# Debugger.net
KiCad netlist of a schematic drawn in Altium Designer
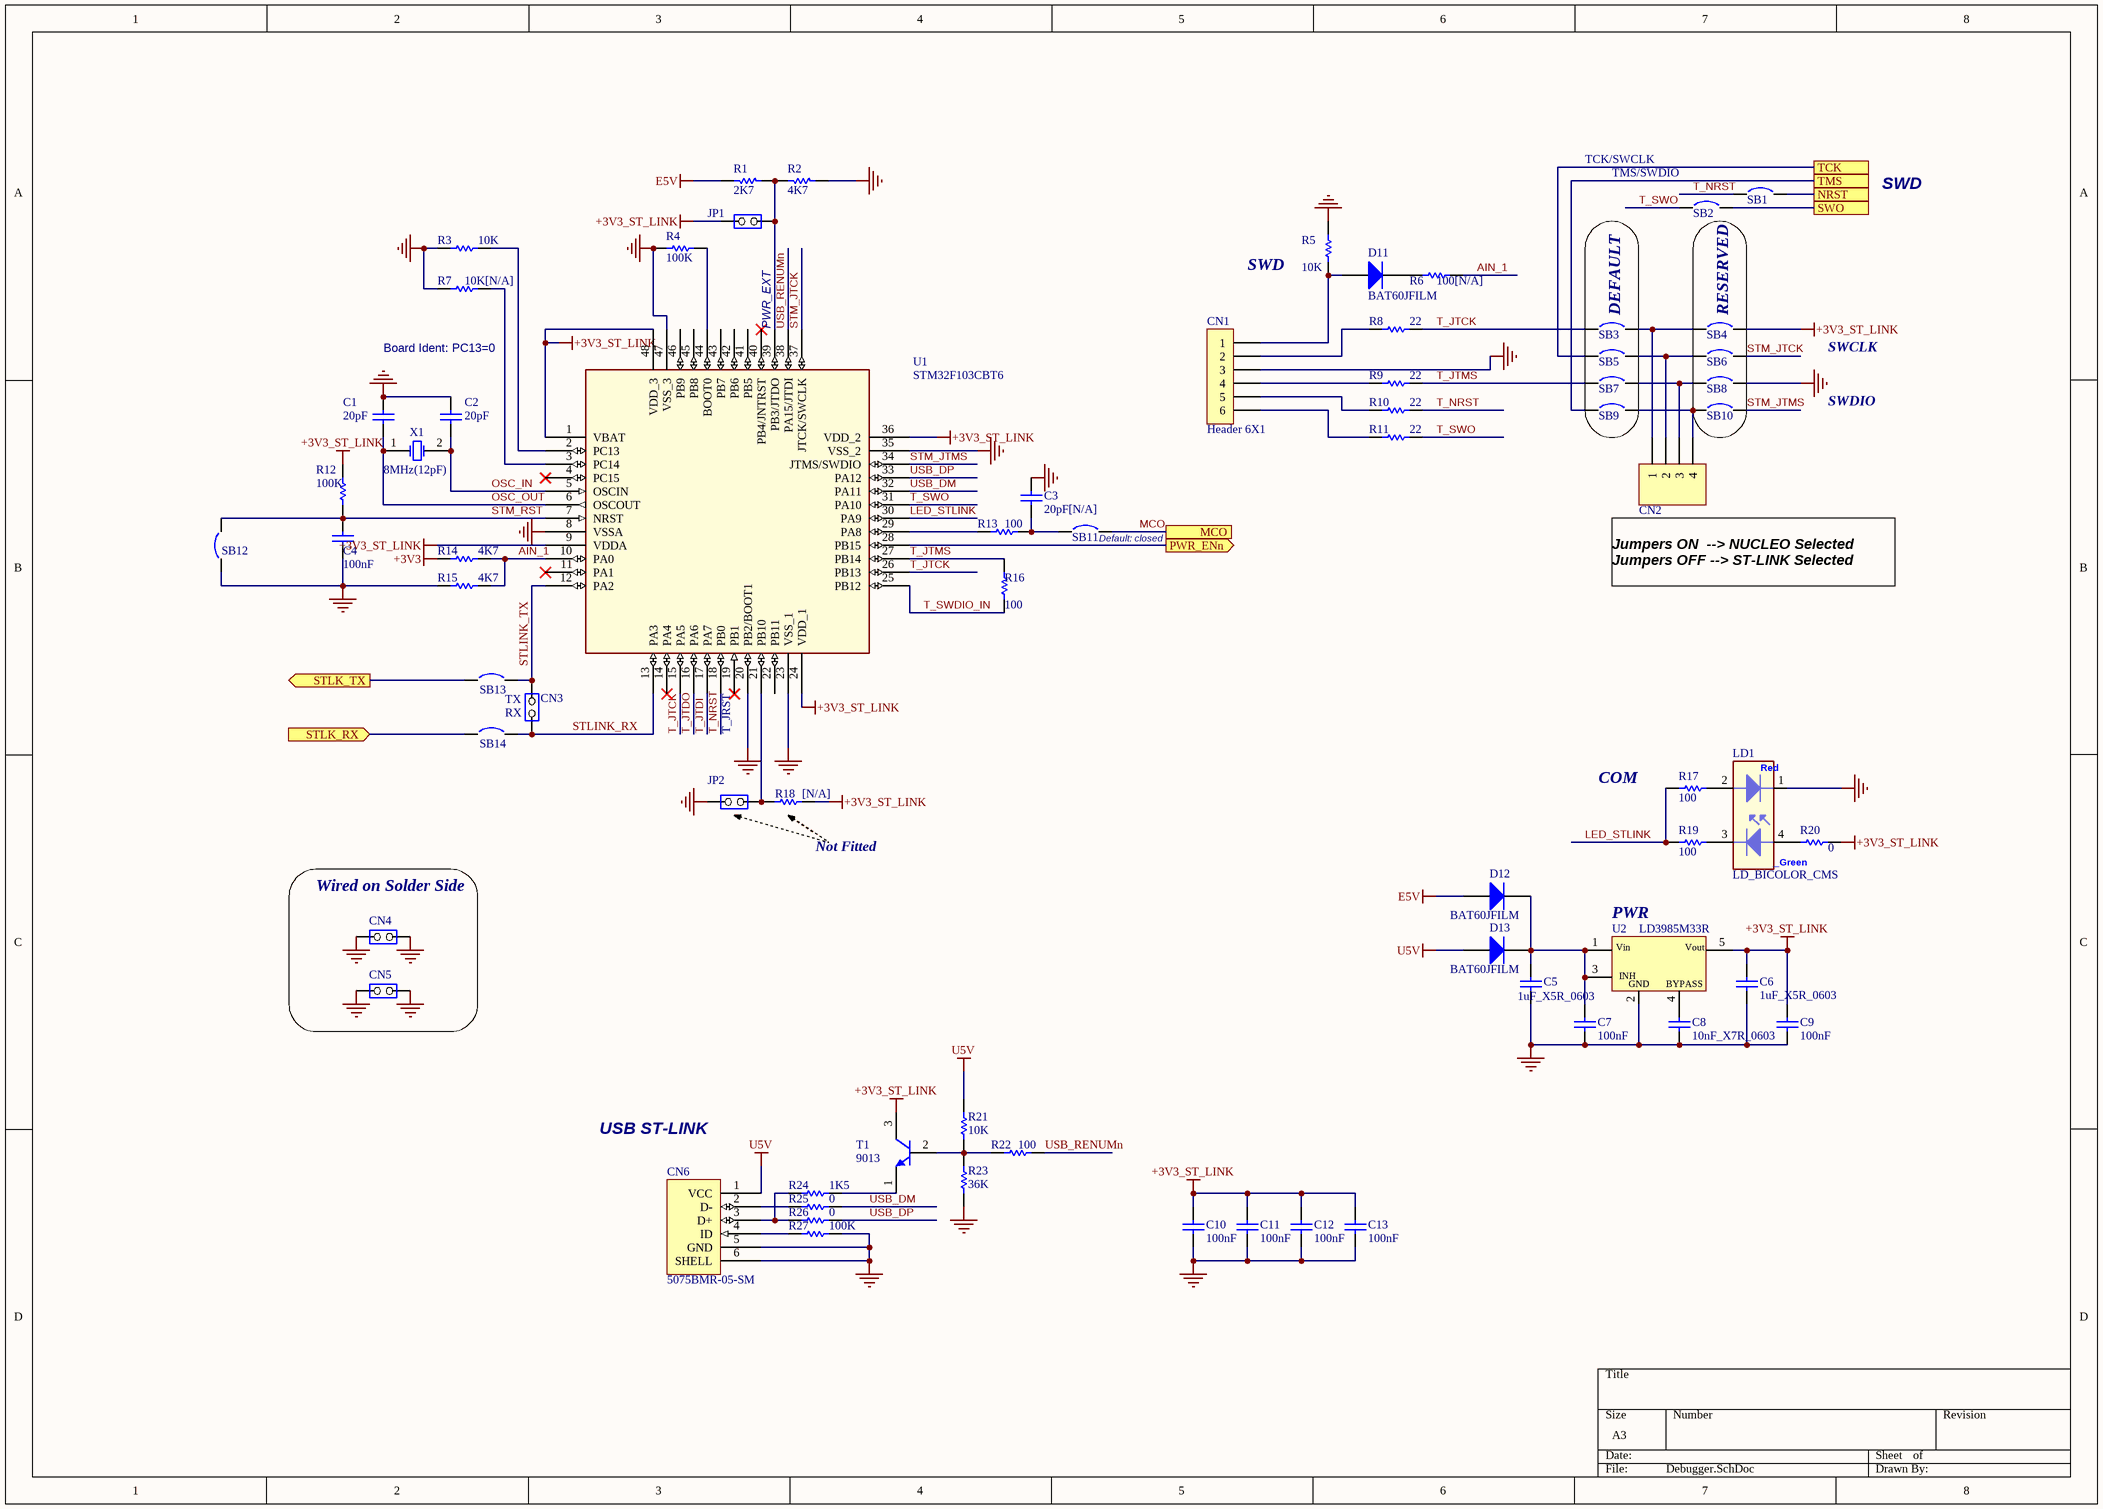
[diagram p0: Debugger.SchDoc]

(export (version "E")
  (design (tool "Eeschema 10.0.6"))
  (components
    (comp (ref "C1")
      (value "20pF")
      (footprint "0603C")
      (description "Capacitor 0402 / 0603 / 0805")
      (libsource (lib "MCD_TOOLS") (part "Capacitor_ST"))
    )
    (comp (ref "C2")
      (value "20pF")
      (footprint "0603C")
      (description "Capacitor 0402 / 0603 / 0805")
      (libsource (lib "MCD_TOOLS") (part "Capacitor_ST"))
    )
    (comp (ref "C3")
      (value "20pF[N/A]")
      (footprint "0603C")
      (description "Capacitor 0402 / 0603 / 0805")
      (libsource (lib "MCD_TOOLS") (part "Capacitor_ST"))
    )
    (comp (ref "C4")
      (value "100nF")
      (footprint "0603C")
      (description "Capacitor 0402 / 0603 / 0805")
      (libsource (lib "MCD_TOOLS") (part "Capacitor_ST"))
    )
    (comp (ref "C5")
      (value "1uF_X5R_0603")
      (footprint "0603C")
      (description "0603  X5R 1µF")
      (fields (field (name "TOLERANCE") "10%"))
      (libsource (lib "MB963_1") (part "CAP SMD 0603  X5R 1µF 25V 10%"))
    )
    (comp (ref "C6")
      (value "1uF_X5R_0603")
      (footprint "0603C")
      (description "0603  X5R 1µF")
      (fields (field (name "TOLERANCE") "10%"))
      (libsource (lib "MB963_1") (part "CAP SMD 0603  X5R 1µF 25V 10%"))
    )
    (comp (ref "C7")
      (value "100nF")
      (footprint "0603C")
      (description "Capacitor 0402 / 0603 / 0805")
      (libsource (lib "MCD_TOOLS") (part "Capacitor_ST"))
    )
    (comp (ref "C8")
      (value "10nF_X7R_0603")
      (footprint "0603C")
      (description "0603  X7R 10NF")
      (fields (field (name "TOLERANCE") "10%"))
      (libsource (lib "MB963_1") (part "CAP SMD 0603  X7R 10000PF 50V 10%"))
    )
    (comp (ref "C9")
      (value "100nF")
      (footprint "0603C")
      (description "Capacitor 0402 / 0603 / 0805")
      (libsource (lib "MCD_TOOLS") (part "Capacitor_ST"))
    )
    (comp (ref "C10")
      (value "100nF")
      (footprint "0603C")
      (description "Capacitor 0402 / 0603 / 0805")
      (libsource (lib "MCD_TOOLS") (part "Capacitor_ST"))
    )
    (comp (ref "C11")
      (value "100nF")
      (footprint "0603C")
      (description "Capacitor 0402 / 0603 / 0805")
      (libsource (lib "MCD_TOOLS") (part "Capacitor_ST"))
    )
    (comp (ref "C12")
      (value "100nF")
      (footprint "0603C")
      (description "Capacitor 0402 / 0603 / 0805")
      (libsource (lib "MCD_TOOLS") (part "Capacitor_ST"))
    )
    (comp (ref "C13")
      (value "100nF")
      (footprint "0603C")
      (description "Capacitor 0402 / 0603 / 0805")
      (libsource (lib "MCD_TOOLS") (part "Capacitor_ST"))
    )
    (comp (ref "CN1")
      (value "Header 6X1")
      (footprint "1*6P")
      (description "Header, 6-Pin, Single row")
      (fields (field (name "PUBLISHER") "Altium Limited"))
      (libsource (lib "Nucleo_64") (part "Header 6X1"))
    )
    (comp (ref "CN2")
      (value "Header 4")
      (footprint "1*4")
      (description "Header, 4-Pin, Single row")
      (fields (field (name "PUBLISHER") "Altium Limited"))
      (libsource (lib "Nucleo_64") (part "Header 4"))
    )
    (comp (ref "CN3") (value "~") (footprint "SIP2/2.54") (libsource (lib "MCD_TOOLS") (part "JP2")))
    (comp (ref "CN4") (value "~") (footprint "SIP2/2.54") (libsource (lib "*") (part "JP2")))
    (comp (ref "CN5") (value "~") (footprint "SIP2/2.54") (libsource (lib "*") (part "JP2")))
    (comp (ref "CN6")
      (value "5075BMR-05-SM")
      (footprint "USB-MINI-B-SMD")
      (description "USB-MINI-typeB connector")
      (libsource (lib "MCD_TOOLS") (part "USB-MINI-typeB connector"))
    )
    (comp (ref "D11")
      (value "BAT60JFILM")
      (footprint "SOD323/A")
      (libsource (lib "MCD_TOOLS") (part "BAT60JFILM"))
    )
    (comp (ref "D12")
      (value "BAT60JFILM")
      (footprint "SOD323/A")
      (libsource (lib "MCD_TOOLS") (part "BAT60JFILM"))
    )
    (comp (ref "D13")
      (value "BAT60JFILM")
      (footprint "SOD323/A")
      (libsource (lib "MCD_TOOLS") (part "BAT60JFILM"))
    )
    (comp (ref "JP1") (value "~") (footprint "SIP2/2.54") (libsource (lib "*") (part "JP2")))
    (comp (ref "JP2") (value "~") (footprint "SIP2/2.54") (libsource (lib "*") (part "JP2")))
    (comp (ref "LD1")
      (value "LD_BICOLOR_CMS")
      (footprint "HSMF-A201")
      (description "Bicolor Led")
      (libsource (lib "MCD_TOOLS") (part "LD_BICOLOR_CMS"))
    )
    (comp (ref "R1")
      (value "2K7")
      (footprint "0603R")
      (description "Resistor")
      (fields (field (name "PUBLISHER") "Altium Limited"))
      (libsource (lib "Miscellaneous Devices") (part "Res1"))
    )
    (comp (ref "R2")
      (value "4K7")
      (footprint "0603R")
      (description "Resistor")
      (fields (field (name "PUBLISHER") "Altium Limited"))
      (libsource (lib "Miscellaneous Devices") (part "Res1"))
    )
    (comp (ref "R3")
      (value "10K")
      (footprint "0603R")
      (description "Resistor 0402 / 0603 / 0805")
      (libsource (lib "") (part "Res1_2"))
    )
    (comp (ref "R4")
      (value "100K")
      (footprint "0603R")
      (description "Resistor 0402 / 0603 / 0805")
      (libsource (lib "") (part "Res1_2"))
    )
    (comp (ref "R5")
      (value "10K")
      (footprint "0603R")
      (description "Resistor 0402 / 0603 / 0805")
      (libsource (lib "") (part "Res1_2"))
    )
    (comp (ref "R6")
      (value "100[N/A]")
      (footprint "0603R")
      (description "Resistor 0402 / 0603 / 0805")
      (libsource (lib "") (part "Res1_2"))
    )
    (comp (ref "R7")
      (value "10K[N/A]")
      (footprint "0603R")
      (description "Resistor 0402 / 0603 / 0805")
      (libsource (lib "") (part "Res1_2"))
    )
    (comp (ref "R8")
      (value "22")
      (footprint "0603R")
      (description "Resistor 0402 / 0603 / 0805")
      (libsource (lib "") (part "Res1_2"))
    )
    (comp (ref "R9")
      (value "22")
      (footprint "0603R")
      (description "Resistor 0402 / 0603 / 0805")
      (libsource (lib "") (part "Res1_2"))
    )
    (comp (ref "R10")
      (value "22")
      (footprint "0603R")
      (description "Resistor 0402 / 0603 / 0805")
      (libsource (lib "") (part "Res1_2"))
    )
    (comp (ref "R11")
      (value "22")
      (footprint "0603R")
      (description "Resistor 0402 / 0603 / 0805")
      (libsource (lib "") (part "Res1_2"))
    )
    (comp (ref "R12")
      (value "100K")
      (footprint "0603R")
      (description "Resistor 0402 / 0603 / 0805")
      (libsource (lib "") (part "Res1_2"))
    )
    (comp (ref "R13")
      (value "100")
      (footprint "0603R")
      (description "Resistor 0402 / 0603 / 0805")
      (libsource (lib "") (part "Res1_2"))
    )
    (comp (ref "R14")
      (value "4K7")
      (footprint "0603R")
      (description "Resistor 0402 / 0603 / 0805")
      (libsource (lib "") (part "Res1_2"))
    )
    (comp (ref "R15")
      (value "4K7")
      (footprint "0603R")
      (description "Resistor 0402 / 0603 / 0805")
      (libsource (lib "") (part "Res1_2"))
    )
    (comp (ref "R16")
      (value "100")
      (footprint "0603R")
      (description "Resistor 0402 / 0603 / 0805")
      (libsource (lib "") (part "Res1_2"))
    )
    (comp (ref "R17")
      (value "100")
      (footprint "0603R")
      (description "Resistor 0402 / 0603 / 0805")
      (libsource (lib "") (part "Res1_2"))
    )
    (comp (ref "R18")
      (value "[N/A]")
      (footprint "0603R")
      (description "Resistor")
      (fields (field (name "PUBLISHER") "Altium Limited"))
      (libsource (lib "") (part "Res1_1"))
    )
    (comp (ref "R19")
      (value "100")
      (footprint "0603R")
      (description "Resistor 0402 / 0603 / 0805")
      (libsource (lib "") (part "Res1_2"))
    )
    (comp (ref "R20")
      (value "0")
      (footprint "0603R")
      (description "Resistor 0402 / 0603 / 0805")
      (libsource (lib "") (part "Res1_2"))
    )
    (comp (ref "R21")
      (value "10K")
      (footprint "0603R")
      (description "Resistor")
      (fields (field (name "PUBLISHER") "Altium Limited"))
      (libsource (lib "") (part "Res1_1"))
    )
    (comp (ref "R22")
      (value "100")
      (footprint "0603R")
      (description "Resistor 0402 / 0603 / 0805")
      (libsource (lib "") (part "Res1_2"))
    )
    (comp (ref "R23")
      (value "36K")
      (footprint "0603R")
      (description "Resistor")
      (fields (field (name "PUBLISHER") "Altium Limited"))
      (libsource (lib "") (part "Res1_1"))
    )
    (comp (ref "R24")
      (value "1K5")
      (footprint "0603R")
      (description "Resistor 0402 / 0603 / 0805")
      (libsource (lib "") (part "Res1_2"))
    )
    (comp (ref "R25")
      (value "0")
      (footprint "0603R")
      (description "Resistor 0402 / 0603 / 0805")
      (libsource (lib "") (part "Res1_2"))
    )
    (comp (ref "R26")
      (value "0")
      (footprint "0603R")
      (description "Resistor 0402 / 0603 / 0805")
      (libsource (lib "") (part "Res1_2"))
    )
    (comp (ref "R27")
      (value "100K")
      (footprint "0603R")
      (description "Resistor 0402 / 0603 / 0805")
      (libsource (lib "") (part "Res1_2"))
    )
    (comp (ref "SB1")
      (value "Circuit Breaker")
      (footprint "JP2_SMD")
      (fields (field (name "PUBLISHER") "Altium Limited"))
      (libsource (lib "MB915") (part "Circuit Breaker"))
    )
    (comp (ref "SB2")
      (value "Circuit Breaker")
      (footprint "JP2_SMD")
      (fields (field (name "PUBLISHER") "Altium Limited"))
      (libsource (lib "MCD_TOOLS") (part "Circuit Breaker"))
    )
    (comp (ref "SB3")
      (value "Circuit Breaker")
      (footprint "JP2_SMD")
      (fields (field (name "PUBLISHER") "Altium Limited"))
      (libsource (lib "MB915") (part "Circuit Breaker"))
    )
    (comp (ref "SB4")
      (value "Circuit Breaker")
      (footprint "JP2_SMD")
      (fields (field (name "PUBLISHER") "Altium Limited"))
      (libsource (lib "MB915") (part "Circuit Breaker"))
    )
    (comp (ref "SB5")
      (value "Circuit Breaker")
      (footprint "JP2_SMD")
      (fields (field (name "PUBLISHER") "Altium Limited"))
      (libsource (lib "MB915") (part "Circuit Breaker"))
    )
    (comp (ref "SB6")
      (value "Circuit Breaker")
      (footprint "JP2_SMD")
      (fields (field (name "PUBLISHER") "Altium Limited"))
      (libsource (lib "MB915") (part "Circuit Breaker"))
    )
    (comp (ref "SB7")
      (value "Circuit Breaker")
      (footprint "JP2_SMD")
      (fields (field (name "PUBLISHER") "Altium Limited"))
      (libsource (lib "MB915") (part "Circuit Breaker"))
    )
    (comp (ref "SB8")
      (value "Circuit Breaker")
      (footprint "JP2_SMD")
      (fields (field (name "PUBLISHER") "Altium Limited"))
      (libsource (lib "MB915") (part "Circuit Breaker"))
    )
    (comp (ref "SB9")
      (value "Circuit Breaker")
      (footprint "JP2_SMD")
      (fields (field (name "PUBLISHER") "Altium Limited"))
      (libsource (lib "MB915") (part "Circuit Breaker"))
    )
    (comp (ref "SB10")
      (value "Circuit Breaker")
      (footprint "JP2_SMD")
      (fields (field (name "PUBLISHER") "Altium Limited"))
      (libsource (lib "MB915") (part "Circuit Breaker"))
    )
    (comp (ref "SB11")
      (value "Circuit Breaker")
      (footprint "JP2_SMD")
      (fields (field (name "PUBLISHER") "Altium Limited"))
      (libsource (lib "MCD_TOOLS") (part "Circuit Breaker"))
    )
    (comp (ref "SB12")
      (value "Circuit Breaker")
      (footprint "JP2_SMD")
      (fields (field (name "PUBLISHER") "Altium Limited"))
      (libsource (lib "MB915") (part "Circuit Breaker"))
    )
    (comp (ref "SB13")
      (value "Circuit Breaker")
      (footprint "JP2_SMD")
      (fields (field (name "PUBLISHER") "Altium Limited"))
      (libsource (lib "MCD_TOOLS") (part "Circuit Breaker"))
    )
    (comp (ref "SB14")
      (value "Circuit Breaker")
      (footprint "JP2_SMD")
      (fields (field (name "PUBLISHER") "Altium Limited"))
      (libsource (lib "MCD_TOOLS") (part "Circuit Breaker"))
    )
    (comp (ref "T1")
      (value "9013")
      (footprint "SOT-23")
      (description "NPN Bipolar Transistor")
      (fields (field (name "PUBLISHER") "Altium Limited"))
      (libsource (lib "Miscellaneous Devices") (part "NPN"))
    )
    (comp (ref "U1")
      (value "STM32F103CBT6")
      (footprint "QFP48 7X7")
      (description "Medium-density performance line ARM-based 32-bit MCU with 64KB Flash")
      (libsource (lib "Nucleo_64") (part "STM32F103CBT6"))
    )
    (comp (ref "U2")
      (value "LD3985M33R")
      (footprint "SOT-23-5L")
      (description "Ultra low drop-low noise BiCMOS voltage, regulators low ESR capacitors compatible")
      (libsource (lib "MCD_TOOLS") (part "LD3985M33R"))
    )
    (comp (ref "X1")
      (value "8MHz(12pF)")
      (footprint "XTAL1")
      (description "Crystal Oscillator")
      (fields (field (name "PUBLISHER") "Altium Limited"))
      (libsource (lib "MB963_1") (part "XTAL"))
    )
  )
  (nets
    (net (code "1") (name "+3V3") (class "Default")
      (node (ref "R14") (pin "1") (pinfunction "1_1") (pintype "passive"))
    )
    (net (code "2") (name "+3V3_ST_LINK") (class "Default")
      (node (ref "C10") (pin "2") (pinfunction "2_2") (pintype "passive"))
      (node (ref "C11") (pin "2") (pinfunction "2_2") (pintype "passive"))
      (node (ref "C12") (pin "2") (pinfunction "2_2") (pintype "passive"))
      (node (ref "C13") (pin "2") (pinfunction "2_2") (pintype "passive"))
      (node (ref "C6") (pin "1") (pinfunction "1_1") (pintype "passive"))
      (node (ref "C9") (pin "2") (pinfunction "2_2") (pintype "passive"))
      (node (ref "JP1") (pin "1") (pinfunction "COMMON_1") (pintype "passive"))
      (node (ref "R12") (pin "2") (pinfunction "2_2") (pintype "passive"))
      (node (ref "R18") (pin "1") (pinfunction "1_1") (pintype "passive"))
      (node (ref "R20") (pin "2") (pinfunction "2_2") (pintype "passive"))
      (node (ref "SB4") (pin "2") (pinfunction "2_2") (pintype "passive"))
      (node (ref "T1") (pin "3") (pinfunction "C_3") (pintype "passive"))
      (node (ref "U1") (pin "1") (pinfunction "VBAT_1") (pintype "power_in"))
      (node (ref "U1") (pin "24") (pinfunction "VDD_1_24") (pintype "power_in"))
      (node (ref "U1") (pin "36") (pinfunction "VDD_2_36") (pintype "power_in"))
      (node (ref "U1") (pin "48") (pinfunction "VDD_3_48") (pintype "power_in"))
      (node (ref "U1") (pin "9") (pinfunction "VDDA_9") (pintype "power_in"))
      (node (ref "U2") (pin "5") (pinfunction "Vout_5") (pintype "passive"))
    )
    (net (code "3") (name "/AIN_1") (class "Default")
      (node (ref "R14") (pin "2") (pinfunction "2_2") (pintype "passive"))
      (node (ref "R15") (pin "2") (pinfunction "2_2") (pintype "passive"))
      (node (ref "R6") (pin "2") (pinfunction "2_2") (pintype "passive"))
      (node (ref "U1") (pin "10") (pinfunction "PA0_10") (pintype "bidirectional"))
    )
    (net (code "4") (name "/LED_STLINK") (class "Default")
      (node (ref "R17") (pin "1") (pinfunction "1_1") (pintype "passive"))
      (node (ref "R19") (pin "1") (pinfunction "1_1") (pintype "passive"))
      (node (ref "U1") (pin "30") (pinfunction "PA9_30") (pintype "bidirectional"))
    )
    (net (code "5") (name "/MCO") (class "Default")
      (node (ref "SB11") (pin "2") (pinfunction "2_2") (pintype "passive"))
    )
    (net (code "6") (name "/NRST") (class "Default")
      (node (ref "SB1") (pin "2") (pinfunction "2_2") (pintype "passive"))
    )
    (net (code "7") (name "/OSC_IN") (class "Default")
      (node (ref "C2") (pin "1") (pinfunction "1_1") (pintype "passive"))
      (node (ref "U1") (pin "5") (pinfunction "OSCIN_5") (pintype "input"))
      (node (ref "X1") (pin "2") (pinfunction "OSC2_2") (pintype "passive"))
    )
    (net (code "8") (name "/OSC_OUT") (class "Default")
      (node (ref "C1") (pin "1") (pinfunction "1_1") (pintype "passive"))
      (node (ref "U1") (pin "6") (pinfunction "OSCOUT_6") (pintype "output"))
      (node (ref "X1") (pin "1") (pinfunction "OSC1_1") (pintype "passive"))
    )
    (net (code "9") (name "/PWR_ENn") (class "Default")
      (node (ref "U1") (pin "28") (pinfunction "PB15_28") (pintype "bidirectional"))
    )
    (net (code "10") (name "/STLINK_RX") (class "Default")
      (node (ref "CN3") (pin "1") (pinfunction "COMMON_1") (pintype "passive"))
      (node (ref "SB14") (pin "2") (pinfunction "2_2") (pintype "passive"))
      (node (ref "U1") (pin "13") (pinfunction "PA3_13") (pintype "bidirectional"))
    )
    (net (code "11") (name "/STLINK_TX") (class "Default")
      (node (ref "CN3") (pin "2") (pinfunction "NO_2") (pintype "passive"))
      (node (ref "SB13") (pin "2") (pinfunction "2_2") (pintype "passive"))
      (node (ref "U1") (pin "12") (pinfunction "PA2_12") (pintype "bidirectional"))
    )
    (net (code "12") (name "/STLK_RX") (class "Default")
      (node (ref "SB14") (pin "1") (pinfunction "1_1") (pintype "passive"))
    )
    (net (code "13") (name "/STLK_TX") (class "Default")
      (node (ref "SB13") (pin "1") (pinfunction "1_1") (pintype "passive"))
    )
    (net (code "14") (name "/STM_JTCK") (class "Default")
      (node (ref "SB6") (pin "2") (pinfunction "2_2") (pintype "passive"))
      (node (ref "U1") (pin "37") (pinfunction "JTCK/SWCLK_37") (pintype "bidirectional"))
    )
    (net (code "15") (name "/STM_JTMS") (class "Default")
      (node (ref "SB10") (pin "2") (pinfunction "2_2") (pintype "passive"))
      (node (ref "U1") (pin "34") (pinfunction "JTMS/SWDIO_34") (pintype "bidirectional"))
    )
    (net (code "16") (name "/STM_RST") (class "Default")
      (node (ref "C4") (pin "2") (pinfunction "2_2") (pintype "passive"))
      (node (ref "R12") (pin "1") (pinfunction "1_1") (pintype "passive"))
      (node (ref "SB12") (pin "2") (pinfunction "2_2") (pintype "passive"))
      (node (ref "U1") (pin "7") (pinfunction "NRST_7") (pintype "input"))
    )
    (net (code "17") (name "/SWO") (class "Default")
      (node (ref "SB2") (pin "2") (pinfunction "2_2") (pintype "passive"))
    )
    (net (code "18") (name "/TCK") (class "Default")
      (node (ref "SB5") (pin "1") (pinfunction "1_1") (pintype "passive"))
    )
    (net (code "19") (name "/TMS") (class "Default")
      (node (ref "SB9") (pin "1") (pinfunction "1_1") (pintype "passive"))
    )
    (net (code "20") (name "/T_JTCK") (class "Default")
      (node (ref "R8") (pin "2") (pinfunction "2_2") (pintype "passive"))
      (node (ref "SB3") (pin "1") (pinfunction "1_1") (pintype "passive"))
      (node (ref "U1") (pin "15") (pinfunction "PA5_15") (pintype "bidirectional"))
      (node (ref "U1") (pin "26") (pinfunction "PB13_26") (pintype "bidirectional"))
    )
    (net (code "21") (name "/T_JTDI") (class "Default")
      (node (ref "U1") (pin "17") (pinfunction "PA7_17") (pintype "bidirectional"))
    )
    (net (code "22") (name "/T_JTDO") (class "Default")
      (node (ref "U1") (pin "16") (pinfunction "PA6_16") (pintype "bidirectional"))
    )
    (net (code "23") (name "/T_JTMS") (class "Default")
      (node (ref "R16") (pin "2") (pinfunction "2_2") (pintype "passive"))
      (node (ref "R9") (pin "2") (pinfunction "2_2") (pintype "passive"))
      (node (ref "SB7") (pin "1") (pinfunction "1_1") (pintype "passive"))
      (node (ref "U1") (pin "27") (pinfunction "PB14_27") (pintype "bidirectional"))
    )
    (net (code "24") (name "/T_NRST") (class "Default")
      (node (ref "R10") (pin "2") (pinfunction "2_2") (pintype "passive"))
      (node (ref "SB1") (pin "1") (pinfunction "1_1") (pintype "passive"))
      (node (ref "U1") (pin "18") (pinfunction "PB0_18") (pintype "bidirectional"))
    )
    (net (code "25") (name "/T_SWDIO_IN") (class "Default")
      (node (ref "R16") (pin "1") (pinfunction "1_1") (pintype "passive"))
      (node (ref "U1") (pin "25") (pinfunction "PB12_25") (pintype "bidirectional"))
    )
    (net (code "26") (name "/T_SWO") (class "Default")
      (node (ref "R11") (pin "2") (pinfunction "2_2") (pintype "passive"))
      (node (ref "SB2") (pin "1") (pinfunction "1_1") (pintype "passive"))
      (node (ref "U1") (pin "31") (pinfunction "PA10_31") (pintype "bidirectional"))
    )
    (net (code "27") (name "/USB_DM") (class "Default")
      (node (ref "R25") (pin "2") (pinfunction "2_2") (pintype "passive"))
      (node (ref "U1") (pin "32") (pinfunction "PA11_32") (pintype "bidirectional"))
    )
    (net (code "28") (name "/USB_DP") (class "Default")
      (node (ref "R26") (pin "2") (pinfunction "2_2") (pintype "passive"))
      (node (ref "U1") (pin "33") (pinfunction "PA12_33") (pintype "bidirectional"))
    )
    (net (code "29") (name "/USB_RENUMn") (class "Default")
      (node (ref "R22") (pin "2") (pinfunction "2_2") (pintype "passive"))
      (node (ref "U1") (pin "38") (pinfunction "PA15/JTDI_38") (pintype "bidirectional"))
    )
    (net (code "30") (name "E5V") (class "Default")
      (node (ref "D12") (pin "1") (pinfunction "A_1") (pintype "passive"))
      (node (ref "R1") (pin "1") (pinfunction "1_1") (pintype "passive"))
    )
    (net (code "31") (name "GND") (class "Default")
      (node (ref "C1") (pin "2") (pinfunction "2_2") (pintype "passive"))
      (node (ref "C10") (pin "1") (pinfunction "1_1") (pintype "passive"))
      (node (ref "C11") (pin "1") (pinfunction "1_1") (pintype "passive"))
      (node (ref "C12") (pin "1") (pinfunction "1_1") (pintype "passive"))
      (node (ref "C13") (pin "1") (pinfunction "1_1") (pintype "passive"))
      (node (ref "C2") (pin "2") (pinfunction "2_2") (pintype "passive"))
      (node (ref "C3") (pin "2") (pinfunction "2_2") (pintype "passive"))
      (node (ref "C4") (pin "1") (pinfunction "1_1") (pintype "passive"))
      (node (ref "C5") (pin "1") (pinfunction "1_1") (pintype "passive"))
      (node (ref "C6") (pin "2") (pinfunction "2_2") (pintype "passive"))
      (node (ref "C7") (pin "1") (pinfunction "1_1") (pintype "passive"))
      (node (ref "C8") (pin "1") (pinfunction "1_1") (pintype "passive"))
      (node (ref "C9") (pin "1") (pinfunction "1_1") (pintype "passive"))
      (node (ref "CN1") (pin "3") (pinfunction "3_3") (pintype "passive"))
      (node (ref "CN4") (pin "1") (pinfunction "COMMON_1") (pintype "passive"))
      (node (ref "CN4") (pin "2") (pinfunction "NO_2") (pintype "passive"))
      (node (ref "CN5") (pin "1") (pinfunction "COMMON_1") (pintype "passive"))
      (node (ref "CN5") (pin "2") (pinfunction "NO_2") (pintype "passive"))
      (node (ref "CN6") (pin "5") (pinfunction "GND_5") (pintype "power_in"))
      (node (ref "CN6") (pin "6") (pinfunction "SHELL_6") (pintype "power_in"))
      (node (ref "JP2") (pin "1") (pinfunction "COMMON_1") (pintype "passive"))
      (node (ref "LD1") (pin "1") (pinfunction "1_1") (pintype "passive"))
      (node (ref "R15") (pin "1") (pinfunction "1_1") (pintype "passive"))
      (node (ref "R2") (pin "2") (pinfunction "2_2") (pintype "passive"))
      (node (ref "R23") (pin "1") (pinfunction "1_1") (pintype "passive"))
      (node (ref "R27") (pin "2") (pinfunction "2_2") (pintype "passive"))
      (node (ref "R3") (pin "1") (pinfunction "1_1") (pintype "passive"))
      (node (ref "R4") (pin "1") (pinfunction "1_1") (pintype "passive"))
      (node (ref "R5") (pin "2") (pinfunction "2_2") (pintype "passive"))
      (node (ref "R7") (pin "1") (pinfunction "1_1") (pintype "passive"))
      (node (ref "SB12") (pin "1") (pinfunction "1_1") (pintype "passive"))
      (node (ref "SB8") (pin "2") (pinfunction "2_2") (pintype "passive"))
      (node (ref "U1") (pin "20") (pinfunction "PB2/BOOT1_20") (pintype "bidirectional"))
      (node (ref "U1") (pin "23") (pinfunction "VSS_1_23") (pintype "power_in"))
      (node (ref "U1") (pin "35") (pinfunction "VSS_2_35") (pintype "power_in"))
      (node (ref "U1") (pin "47") (pinfunction "VSS_3_47") (pintype "power_in"))
      (node (ref "U1") (pin "8") (pinfunction "VSSA_8") (pintype "power_in"))
      (node (ref "U2") (pin "2") (pinfunction "GND_2") (pintype "passive"))
    )
    (net (code "32") (name "Net-(C3-Pad1)") (class "Default")
      (node (ref "C3") (pin "1") (pinfunction "1_1") (pintype "passive"))
      (node (ref "R13") (pin "2") (pinfunction "2_2") (pintype "passive"))
      (node (ref "SB11") (pin "1") (pinfunction "1_1") (pintype "passive"))
    )
    (net (code "33") (name "Net-(CN1-Pad2)") (class "Default")
      (node (ref "CN1") (pin "2") (pinfunction "2_2") (pintype "passive"))
      (node (ref "R8") (pin "1") (pinfunction "1_1") (pintype "passive"))
    )
    (net (code "34") (name "Net-(CN1-Pad4)") (class "Default")
      (node (ref "CN1") (pin "4") (pinfunction "4_4") (pintype "passive"))
      (node (ref "R9") (pin "1") (pinfunction "1_1") (pintype "passive"))
    )
    (net (code "35") (name "Net-(CN1-Pad5)") (class "Default")
      (node (ref "CN1") (pin "5") (pinfunction "5_5") (pintype "passive"))
      (node (ref "R10") (pin "1") (pinfunction "1_1") (pintype "passive"))
    )
    (net (code "36") (name "Net-(CN1-Pad6)") (class "Default")
      (node (ref "CN1") (pin "6") (pinfunction "6_6") (pintype "passive"))
      (node (ref "R11") (pin "1") (pinfunction "1_1") (pintype "passive"))
    )
    (net (code "37") (name "Net-(CN2-Pad1)") (class "Default")
      (node (ref "CN2") (pin "1") (pinfunction "1_1") (pintype "passive"))
      (node (ref "SB3") (pin "2") (pinfunction "2_2") (pintype "passive"))
      (node (ref "SB4") (pin "1") (pinfunction "1_1") (pintype "passive"))
    )
    (net (code "38") (name "Net-(CN2-Pad2)") (class "Default")
      (node (ref "CN2") (pin "2") (pinfunction "2_2") (pintype "passive"))
      (node (ref "SB5") (pin "2") (pinfunction "2_2") (pintype "passive"))
      (node (ref "SB6") (pin "1") (pinfunction "1_1") (pintype "passive"))
    )
    (net (code "39") (name "Net-(CN2-Pad3)") (class "Default")
      (node (ref "CN2") (pin "3") (pinfunction "3_3") (pintype "passive"))
      (node (ref "SB7") (pin "2") (pinfunction "2_2") (pintype "passive"))
      (node (ref "SB8") (pin "1") (pinfunction "1_1") (pintype "passive"))
    )
    (net (code "40") (name "Net-(CN2-Pad4)") (class "Default")
      (node (ref "CN2") (pin "4") (pinfunction "4_4") (pintype "passive"))
      (node (ref "SB10") (pin "1") (pinfunction "1_1") (pintype "passive"))
      (node (ref "SB9") (pin "2") (pinfunction "2_2") (pintype "passive"))
    )
    (net (code "41") (name "Net-(CN6-D+)") (class "Default")
      (node (ref "CN6") (pin "3") (pinfunction "D+_3") (pintype "bidirectional"))
      (node (ref "R24") (pin "1") (pinfunction "1_1") (pintype "passive"))
      (node (ref "R26") (pin "1") (pinfunction "1_1") (pintype "passive"))
    )
    (net (code "42") (name "Net-(CN6-D-)") (class "Default")
      (node (ref "CN6") (pin "2") (pinfunction "D-_2") (pintype "bidirectional"))
      (node (ref "R25") (pin "1") (pinfunction "1_1") (pintype "passive"))
    )
    (net (code "43") (name "Net-(CN6-ID)") (class "Default")
      (node (ref "CN6") (pin "4") (pinfunction "ID_4") (pintype "input"))
      (node (ref "R27") (pin "1") (pinfunction "1_1") (pintype "passive"))
    )
    (net (code "44") (name "Net-(D11-A)") (class "Default")
      (node (ref "CN1") (pin "1") (pinfunction "1_1") (pintype "passive"))
      (node (ref "D11") (pin "1") (pinfunction "A_1") (pintype "passive"))
      (node (ref "R5") (pin "1") (pinfunction "1_1") (pintype "passive"))
    )
    (net (code "45") (name "Net-(D11-K)") (class "Default")
      (node (ref "D11") (pin "2") (pinfunction "K_2") (pintype "passive"))
      (node (ref "R6") (pin "1") (pinfunction "1_1") (pintype "passive"))
    )
    (net (code "46") (name "Net-(D12-K)") (class "Default")
      (node (ref "C5") (pin "2") (pinfunction "2_2") (pintype "passive"))
      (node (ref "C7") (pin "2") (pinfunction "2_2") (pintype "passive"))
      (node (ref "D12") (pin "2") (pinfunction "K_2") (pintype "passive"))
      (node (ref "D13") (pin "2") (pinfunction "K_2") (pintype "passive"))
      (node (ref "U2") (pin "1") (pinfunction "Vin_1") (pintype "passive"))
      (node (ref "U2") (pin "3") (pinfunction "CE_3") (pintype "passive"))
    )
    (net (code "47") (name "Net-(JP1-NO)") (class "Default")
      (node (ref "JP1") (pin "2") (pinfunction "NO_2") (pintype "passive"))
      (node (ref "R1") (pin "2") (pinfunction "2_2") (pintype "passive"))
      (node (ref "R2") (pin "1") (pinfunction "1_1") (pintype "passive"))
      (node (ref "U1") (pin "39") (pinfunction "PB3/JTDO_39") (pintype "bidirectional"))
    )
    (net (code "48") (name "Net-(JP2-NO)") (class "Default")
      (node (ref "JP2") (pin "2") (pinfunction "NO_2") (pintype "passive"))
      (node (ref "R18") (pin "2") (pinfunction "2_2") (pintype "passive"))
      (node (ref "U1") (pin "21") (pinfunction "PB10_21") (pintype "bidirectional"))
    )
    (net (code "49") (name "Net-(LD1-Pad2)") (class "Default")
      (node (ref "LD1") (pin "2") (pinfunction "2_2") (pintype "passive"))
      (node (ref "R17") (pin "2") (pinfunction "2_2") (pintype "passive"))
    )
    (net (code "50") (name "Net-(LD1-Pad3)") (class "Default")
      (node (ref "LD1") (pin "3") (pinfunction "3_3") (pintype "passive"))
      (node (ref "R19") (pin "2") (pinfunction "2_2") (pintype "passive"))
    )
    (net (code "51") (name "Net-(LD1-Pad4)") (class "Default")
      (node (ref "LD1") (pin "4") (pinfunction "4_4") (pintype "passive"))
      (node (ref "R20") (pin "1") (pinfunction "1_1") (pintype "passive"))
    )
    (net (code "52") (name "Net-(T1-B)") (class "Default")
      (node (ref "R21") (pin "1") (pinfunction "1_1") (pintype "passive"))
      (node (ref "R22") (pin "1") (pinfunction "1_1") (pintype "passive"))
      (node (ref "R23") (pin "2") (pinfunction "2_2") (pintype "passive"))
      (node (ref "T1") (pin "2") (pinfunction "B_2") (pintype "passive"))
    )
    (net (code "53") (name "Net-(T1-E)") (class "Default")
      (node (ref "R24") (pin "2") (pinfunction "2_2") (pintype "passive"))
      (node (ref "T1") (pin "1") (pinfunction "E_1") (pintype "passive"))
    )
    (net (code "54") (name "Net-(U1-BOOT0)") (class "Default")
      (node (ref "R4") (pin "2") (pinfunction "2_2") (pintype "passive"))
      (node (ref "U1") (pin "44") (pinfunction "BOOT0_44") (pintype "bidirectional"))
    )
    (net (code "55") (name "Net-(U1-PA8)") (class "Default")
      (node (ref "R13") (pin "1") (pinfunction "1_1") (pintype "passive"))
      (node (ref "U1") (pin "29") (pinfunction "PA8_29") (pintype "bidirectional"))
    )
    (net (code "56") (name "Net-(U1-PC13)") (class "Default")
      (node (ref "R3") (pin "2") (pinfunction "2_2") (pintype "passive"))
      (node (ref "U1") (pin "2") (pinfunction "PC13_2") (pintype "bidirectional"))
    )
    (net (code "57") (name "Net-(U1-PC14)") (class "Default")
      (node (ref "R7") (pin "2") (pinfunction "2_2") (pintype "passive"))
      (node (ref "U1") (pin "3") (pinfunction "PC14_3") (pintype "bidirectional"))
    )
    (net (code "58") (name "Net-(U2-BYPASS)") (class "Default")
      (node (ref "C8") (pin "2") (pinfunction "2_2") (pintype "passive"))
      (node (ref "U2") (pin "4") (pinfunction "BYPASS_4") (pintype "passive"))
    )
    (net (code "59") (name "U5V") (class "Default")
      (node (ref "CN6") (pin "1") (pinfunction "VCC_1") (pintype "power_in"))
      (node (ref "D13") (pin "1") (pinfunction "A_1") (pintype "passive"))
      (node (ref "R21") (pin "2") (pinfunction "2_2") (pintype "passive"))
    )
    (net (code "60") (name "unconnected-(U1-PA1-Pad11)") (class "Default")
      (node (ref "U1") (pin "11") (pinfunction "PA1_11") (pintype "bidirectional+no_connect"))
    )
    (net (code "61") (name "unconnected-(U1-PA4-Pad14)") (class "Default")
      (node (ref "U1") (pin "14") (pinfunction "PA4_14") (pintype "bidirectional+no_connect"))
    )
    (net (code "62") (name "unconnected-(U1-PB1-Pad19)") (class "Default")
      (node (ref "U1") (pin "19") (pinfunction "PB1_19") (pintype "input+no_connect"))
    )
    (net (code "63") (name "unconnected-(U1-PB4{slash}JNTRST-Pad40)") (class "Default")
      (node (ref "U1") (pin "40") (pinfunction "PB4/JNTRST_40") (pintype "bidirectional+no_connect"))
    )
    (net (code "64") (name "unconnected-(U1-PB5-Pad41)") (class "Default")
      (node (ref "U1") (pin "41") (pinfunction "PB5_41") (pintype "bidirectional"))
    )
    (net (code "65") (name "unconnected-(U1-PB6-Pad42)") (class "Default")
      (node (ref "U1") (pin "42") (pinfunction "PB6_42") (pintype "bidirectional"))
    )
    (net (code "66") (name "unconnected-(U1-PB7-Pad43)") (class "Default")
      (node (ref "U1") (pin "43") (pinfunction "PB7_43") (pintype "bidirectional"))
    )
    (net (code "67") (name "unconnected-(U1-PB8-Pad45)") (class "Default")
      (node (ref "U1") (pin "45") (pinfunction "PB8_45") (pintype "bidirectional"))
    )
    (net (code "68") (name "unconnected-(U1-PB9-Pad46)") (class "Default")
      (node (ref "U1") (pin "46") (pinfunction "PB9_46") (pintype "bidirectional"))
    )
    (net (code "69") (name "unconnected-(U1-PB11-Pad22)") (class "Default")
      (node (ref "U1") (pin "22") (pinfunction "PB11_22") (pintype "bidirectional"))
    )
    (net (code "70") (name "unconnected-(U1-PC15-Pad4)") (class "Default")
      (node (ref "U1") (pin "4") (pinfunction "PC15_4") (pintype "bidirectional+no_connect"))
    )
  )
)
